# core1.net
KiCad netlist of a schematic drawn in EAGLE
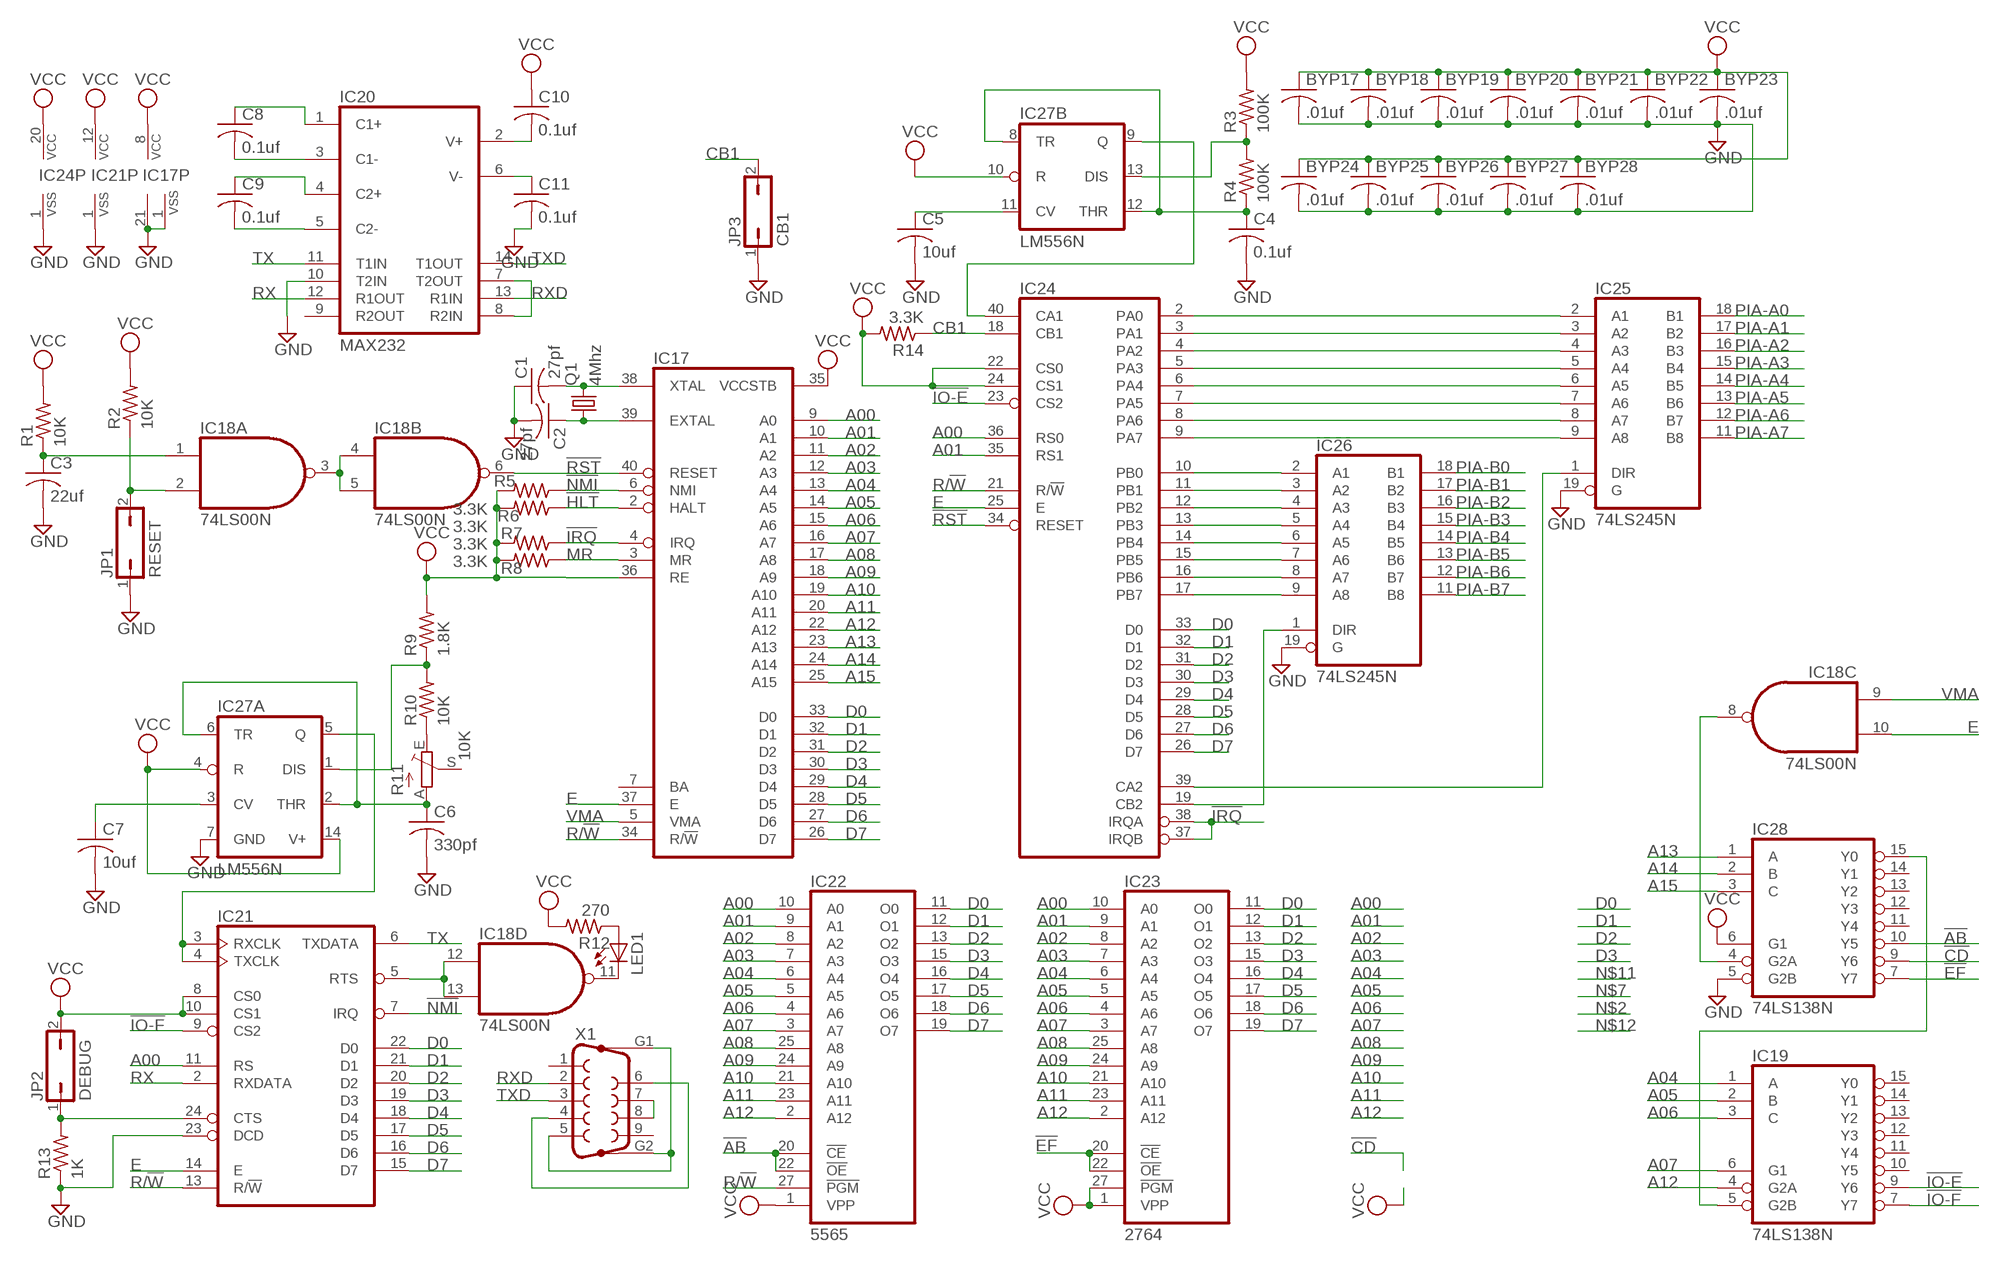
[diagram p0: schematic, sheet 1]
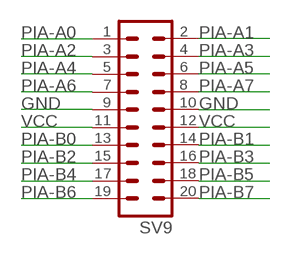
[diagram p1: schematic, sheet 2]

(export (version "E")
  (design (tool "Eeschema 10.0.6"))
  (components
    (comp (ref "BYP17")
      (value ".01uf")
      (footprint "eagle-import:C050-025X075")
      (libsource (lib "eagle-import") (part "C-US050-025X075"))
    )
    (comp (ref "BYP18")
      (value ".01uf")
      (footprint "eagle-import:C050-025X075")
      (libsource (lib "eagle-import") (part "C-US050-025X075"))
    )
    (comp (ref "BYP19")
      (value ".01uf")
      (footprint "eagle-import:C050-025X075")
      (libsource (lib "eagle-import") (part "C-US050-025X075"))
    )
    (comp (ref "BYP20")
      (value ".01uf")
      (footprint "eagle-import:C050-025X075")
      (libsource (lib "eagle-import") (part "C-US050-025X075"))
    )
    (comp (ref "BYP21")
      (value ".01uf")
      (footprint "eagle-import:C050-025X075")
      (libsource (lib "eagle-import") (part "C-US050-025X075"))
    )
    (comp (ref "BYP22")
      (value ".01uf")
      (footprint "eagle-import:C050-025X075")
      (libsource (lib "eagle-import") (part "C-US050-025X075"))
    )
    (comp (ref "BYP23")
      (value ".01uf")
      (footprint "eagle-import:C050-025X075")
      (libsource (lib "eagle-import") (part "C-US050-025X075"))
    )
    (comp (ref "BYP24")
      (value ".01uf")
      (footprint "eagle-import:C050-025X075")
      (libsource (lib "eagle-import") (part "C-US050-025X075"))
    )
    (comp (ref "BYP25")
      (value ".01uf")
      (footprint "eagle-import:C050-025X075")
      (libsource (lib "eagle-import") (part "C-US050-025X075"))
    )
    (comp (ref "BYP26")
      (value ".01uf")
      (footprint "eagle-import:C050-025X075")
      (libsource (lib "eagle-import") (part "C-US050-025X075"))
    )
    (comp (ref "BYP27")
      (value ".01uf")
      (footprint "eagle-import:C050-025X075")
      (libsource (lib "eagle-import") (part "C-US050-025X075"))
    )
    (comp (ref "BYP28")
      (value ".01uf")
      (footprint "eagle-import:C050-025X075")
      (libsource (lib "eagle-import") (part "C-US050-025X075"))
    )
    (comp (ref "C1")
      (value "27pf")
      (footprint "eagle-import:C050-025X075")
      (libsource (lib "eagle-import") (part "C-US050-025X075"))
    )
    (comp (ref "C2")
      (value "27pf")
      (footprint "eagle-import:C050-025X075")
      (libsource (lib "eagle-import") (part "C-US050-025X075"))
    )
    (comp (ref "C3")
      (value "22uf")
      (footprint "eagle-import:C102-043X133")
      (libsource (lib "eagle-import") (part "C-US102-043X133"))
    )
    (comp (ref "C4")
      (value "0.1uf")
      (footprint "eagle-import:C050-025X075")
      (libsource (lib "eagle-import") (part "C-US050-025X075"))
    )
    (comp (ref "C5")
      (value "10uf")
      (footprint "eagle-import:C050-025X075")
      (libsource (lib "eagle-import") (part "C-US050-025X075"))
    )
    (comp (ref "C6")
      (value "330pf")
      (footprint "eagle-import:C050-025X075")
      (libsource (lib "eagle-import") (part "C-US050-025X075"))
    )
    (comp (ref "C7")
      (value "10uf")
      (footprint "eagle-import:C050-025X075")
      (libsource (lib "eagle-import") (part "C-US050-025X075"))
    )
    (comp (ref "C8")
      (value "0.1uf")
      (footprint "eagle-import:C050-025X075")
      (libsource (lib "eagle-import") (part "C-US050-025X075"))
    )
    (comp (ref "C9")
      (value "0.1uf")
      (footprint "eagle-import:C050-025X075")
      (libsource (lib "eagle-import") (part "C-US050-025X075"))
    )
    (comp (ref "C10")
      (value "0.1uf")
      (footprint "eagle-import:C050-025X075")
      (libsource (lib "eagle-import") (part "C-US050-025X075"))
    )
    (comp (ref "C11")
      (value "0.1uf")
      (footprint "eagle-import:C050-025X075")
      (libsource (lib "eagle-import") (part "C-US050-025X075"))
    )
    (comp (ref "IC17")
      (value "6802")
      (footprint "eagle-import:DIL40")
      (libsource (lib "eagle-import") (part "6802"))
    )
    (comp (ref "IC18")
      (value "74LS00N")
      (footprint "eagle-import:DIL14")
      (libsource (lib "eagle-import") (part "7400NLS"))
    )
    (comp (ref "IC19")
      (value "74LS138N")
      (footprint "eagle-import:DIL16")
      (libsource (lib "eagle-import") (part "74138NLS"))
    )
    (comp (ref "IC20")
      (value "MAX232")
      (footprint "eagle-import:DIL16")
      (fields (field (name "MF") "MAXIM") (field (name "MPN") "MAX232ACPE+"))
      (libsource (lib "eagle-import") (part "MAX232"))
    )
    (comp (ref "IC21")
      (value "6850")
      (footprint "eagle-import:DIL24")
      (fields (field (name "MF") "NTE ELECTRONICS") (field (name "MPN") "NTE6850"))
      (libsource (lib "eagle-import") (part "6850"))
    )
    (comp (ref "IC22")
      (value "5565")
      (footprint "eagle-import:DIL28")
      (libsource (lib "eagle-import") (part "2764"))
    )
    (comp (ref "IC23")
      (value "2764")
      (footprint "eagle-import:DIL28")
      (libsource (lib "eagle-import") (part "2764"))
    )
    (comp (ref "IC24")
      (value "6821")
      (footprint "eagle-import:DIL40")
      (fields (field (name "MF") "NTE ELECTRONICS") (field (name "MPN") "NTE6821"))
      (libsource (lib "eagle-import") (part "6821"))
    )
    (comp (ref "IC25")
      (value "74LS245N")
      (footprint "eagle-import:DIL20")
      (libsource (lib "eagle-import") (part "74245NLS"))
    )
    (comp (ref "IC26")
      (value "74LS245N")
      (footprint "eagle-import:DIL20")
      (libsource (lib "eagle-import") (part "74245NLS"))
    )
    (comp (ref "IC27")
      (value "LM556N")
      (footprint "eagle-import:DIL14")
      (libsource (lib "eagle-import") (part "556NLM"))
    )
    (comp (ref "IC28")
      (value "74LS138N")
      (footprint "eagle-import:DIL16")
      (libsource (lib "eagle-import") (part "74138NLS"))
    )
    (comp (ref "JP1")
      (value "RESET")
      (footprint "eagle-import:JP1")
      (libsource (lib "eagle-import") (part "JP1Q"))
    )
    (comp (ref "JP2")
      (value "DEBUG")
      (footprint "eagle-import:JP1")
      (libsource (lib "eagle-import") (part "JP1Q"))
    )
    (comp (ref "JP3")
      (value "CB1")
      (footprint "eagle-import:JP1")
      (libsource (lib "eagle-import") (part "JP1Q"))
    )
    (comp (ref "LED1")
      (value "LED3MM")
      (footprint "eagle-import:LED3MM")
      (libsource (lib "eagle-import") (part "LED3MM"))
    )
    (comp (ref "Q1")
      (value "4Mhz")
      (footprint "eagle-import:HC18U-V")
      (libsource (lib "eagle-import") (part "CRYSTALHC18U-V"))
    )
    (comp (ref "R1")
      (value "10K")
      (footprint "eagle-import:0207_7")
      (libsource (lib "eagle-import") (part "R-US_0207/7"))
    )
    (comp (ref "R2")
      (value "10K")
      (footprint "eagle-import:0207_7")
      (libsource (lib "eagle-import") (part "R-US_0207/7"))
    )
    (comp (ref "R3")
      (value "100K")
      (footprint "eagle-import:0207_7")
      (libsource (lib "eagle-import") (part "R-US_0207/7"))
    )
    (comp (ref "R4")
      (value "100K")
      (footprint "eagle-import:0207_7")
      (libsource (lib "eagle-import") (part "R-US_0207/7"))
    )
    (comp (ref "R5")
      (value "3.3K")
      (footprint "eagle-import:0207_7")
      (libsource (lib "eagle-import") (part "R-US_0207/7"))
    )
    (comp (ref "R6")
      (value "3.3K")
      (footprint "eagle-import:0207_7")
      (libsource (lib "eagle-import") (part "R-US_0207/7"))
    )
    (comp (ref "R7")
      (value "3.3K")
      (footprint "eagle-import:0207_7")
      (libsource (lib "eagle-import") (part "R-US_0207/7"))
    )
    (comp (ref "R8")
      (value "3.3K")
      (footprint "eagle-import:0207_7")
      (libsource (lib "eagle-import") (part "R-US_0207/7"))
    )
    (comp (ref "R9")
      (value "1.8K")
      (footprint "eagle-import:0207_7")
      (libsource (lib "eagle-import") (part "R-US_0207/7"))
    )
    (comp (ref "R10")
      (value "10K")
      (footprint "eagle-import:0207_7")
      (libsource (lib "eagle-import") (part "R-US_0207/7"))
    )
    (comp (ref "R11")
      (value "10K")
      (footprint "eagle-import:SP19L")
      (libsource (lib "eagle-import") (part "TRIM_EU-B90P"))
    )
    (comp (ref "R12")
      (value "270")
      (footprint "eagle-import:0207_7")
      (libsource (lib "eagle-import") (part "R-US_0207/7"))
    )
    (comp (ref "R13")
      (value "1K")
      (footprint "eagle-import:0207_7")
      (libsource (lib "eagle-import") (part "R-US_0207/7"))
    )
    (comp (ref "R14")
      (value "3.3K")
      (footprint "eagle-import:0207_7")
      (libsource (lib "eagle-import") (part "R-US_0207/7"))
    )
    (comp (ref "X1")
      (value "F09HP")
      (footprint "eagle-import:F09HP")
      (libsource (lib "eagle-import") (part "F09HP"))
    )
    (comp (ref "SV9")
      (value "MA10-2")
      (footprint "eagle-import:MA10-2")
      (libsource (lib "eagle-import") (part "MA10-2"))
    )
  )
  (nets
    (net (code "1") (name "A00") (class "Default")
      (node (ref "IC17") (pin "9") (pinfunction "A0_9") (pintype "output"))
      (node (ref "IC21") (pin "11") (pinfunction "RS_11") (pintype "input"))
      (node (ref "IC22") (pin "10") (pinfunction "A0_10") (pintype "input"))
      (node (ref "IC23") (pin "10") (pinfunction "A0_10") (pintype "input"))
      (node (ref "IC24") (pin "36") (pinfunction "RS0_36") (pintype "input"))
    )
    (net (code "2") (name "A01") (class "Default")
      (node (ref "IC17") (pin "10") (pinfunction "A1_10") (pintype "output"))
      (node (ref "IC22") (pin "9") (pinfunction "A1_9") (pintype "input"))
      (node (ref "IC23") (pin "9") (pinfunction "A1_9") (pintype "input"))
      (node (ref "IC24") (pin "35") (pinfunction "RS1_35") (pintype "input"))
    )
    (net (code "3") (name "A02") (class "Default")
      (node (ref "IC17") (pin "11") (pinfunction "A2_11") (pintype "output"))
      (node (ref "IC22") (pin "8") (pinfunction "A2_8") (pintype "input"))
      (node (ref "IC23") (pin "8") (pinfunction "A2_8") (pintype "input"))
    )
    (net (code "4") (name "A03") (class "Default")
      (node (ref "IC17") (pin "12") (pinfunction "A3_12") (pintype "output"))
      (node (ref "IC22") (pin "7") (pinfunction "A3_7") (pintype "input"))
      (node (ref "IC23") (pin "7") (pinfunction "A3_7") (pintype "input"))
    )
    (net (code "5") (name "A04") (class "Default")
      (node (ref "IC17") (pin "13") (pinfunction "A4_13") (pintype "output"))
      (node (ref "IC19") (pin "1") (pinfunction "A_1") (pintype "input"))
      (node (ref "IC22") (pin "6") (pinfunction "A4_6") (pintype "input"))
      (node (ref "IC23") (pin "6") (pinfunction "A4_6") (pintype "input"))
    )
    (net (code "6") (name "A05") (class "Default")
      (node (ref "IC17") (pin "14") (pinfunction "A5_14") (pintype "output"))
      (node (ref "IC19") (pin "2") (pinfunction "B_2") (pintype "input"))
      (node (ref "IC22") (pin "5") (pinfunction "A5_5") (pintype "input"))
      (node (ref "IC23") (pin "5") (pinfunction "A5_5") (pintype "input"))
    )
    (net (code "7") (name "A06") (class "Default")
      (node (ref "IC17") (pin "15") (pinfunction "A6_15") (pintype "output"))
      (node (ref "IC19") (pin "3") (pinfunction "C_3") (pintype "input"))
      (node (ref "IC22") (pin "4") (pinfunction "A6_4") (pintype "input"))
      (node (ref "IC23") (pin "4") (pinfunction "A6_4") (pintype "input"))
    )
    (net (code "8") (name "A07") (class "Default")
      (node (ref "IC17") (pin "16") (pinfunction "A7_16") (pintype "output"))
      (node (ref "IC19") (pin "6") (pinfunction "G1_6") (pintype "input"))
      (node (ref "IC22") (pin "3") (pinfunction "A7_3") (pintype "input"))
      (node (ref "IC23") (pin "3") (pinfunction "A7_3") (pintype "input"))
    )
    (net (code "9") (name "A08") (class "Default")
      (node (ref "IC17") (pin "17") (pinfunction "A8_17") (pintype "output"))
      (node (ref "IC22") (pin "25") (pinfunction "A8_25") (pintype "input"))
      (node (ref "IC23") (pin "25") (pinfunction "A8_25") (pintype "input"))
    )
    (net (code "10") (name "A09") (class "Default")
      (node (ref "IC17") (pin "18") (pinfunction "A9_18") (pintype "output"))
      (node (ref "IC22") (pin "24") (pinfunction "A9_24") (pintype "input"))
      (node (ref "IC23") (pin "24") (pinfunction "A9_24") (pintype "input"))
    )
    (net (code "11") (name "A10") (class "Default")
      (node (ref "IC17") (pin "19") (pinfunction "A10_19") (pintype "output"))
      (node (ref "IC22") (pin "21") (pinfunction "A10_21") (pintype "input"))
      (node (ref "IC23") (pin "21") (pinfunction "A10_21") (pintype "input"))
    )
    (net (code "12") (name "A11") (class "Default")
      (node (ref "IC17") (pin "20") (pinfunction "A11_20") (pintype "output"))
      (node (ref "IC22") (pin "23") (pinfunction "A11_23") (pintype "input"))
      (node (ref "IC23") (pin "23") (pinfunction "A11_23") (pintype "input"))
    )
    (net (code "13") (name "A12") (class "Default")
      (node (ref "IC17") (pin "22") (pinfunction "A12_22") (pintype "output"))
      (node (ref "IC19") (pin "4") (pinfunction "G2A_4") (pintype "input"))
      (node (ref "IC22") (pin "2") (pinfunction "A12_2") (pintype "input"))
      (node (ref "IC23") (pin "2") (pinfunction "A12_2") (pintype "input"))
    )
    (net (code "14") (name "A13") (class "Default")
      (node (ref "IC17") (pin "23") (pinfunction "A13_23") (pintype "output"))
      (node (ref "IC28") (pin "1") (pinfunction "A_1") (pintype "input"))
    )
    (net (code "15") (name "A14") (class "Default")
      (node (ref "IC17") (pin "24") (pinfunction "A14_24") (pintype "output"))
      (node (ref "IC28") (pin "2") (pinfunction "B_2") (pintype "input"))
    )
    (net (code "16") (name "A15") (class "Default")
      (node (ref "IC17") (pin "25") (pinfunction "A15_25") (pintype "output"))
      (node (ref "IC28") (pin "3") (pinfunction "C_3") (pintype "input"))
    )
    (net (code "17") (name "CB1") (class "Default")
      (node (ref "IC24") (pin "18") (pinfunction "CB1_18") (pintype "input"))
      (node (ref "JP3") (pin "2") (pinfunction "2_2") (pintype "passive"))
      (node (ref "R14") (pin "1") (pinfunction "1_1") (pintype "passive"))
    )
    (net (code "18") (name "D0") (class "Default")
      (node (ref "IC17") (pin "33") (pinfunction "D0_33") (pintype "bidirectional"))
      (node (ref "IC21") (pin "22") (pinfunction "D0_22") (pintype "bidirectional"))
      (node (ref "IC22") (pin "11") (pinfunction "O0_11") (pintype "tri_state"))
      (node (ref "IC23") (pin "11") (pinfunction "O0_11") (pintype "tri_state"))
      (node (ref "IC24") (pin "33") (pinfunction "D0_33") (pintype "bidirectional"))
    )
    (net (code "19") (name "D1") (class "Default")
      (node (ref "IC17") (pin "32") (pinfunction "D1_32") (pintype "bidirectional"))
      (node (ref "IC21") (pin "21") (pinfunction "D1_21") (pintype "bidirectional"))
      (node (ref "IC22") (pin "12") (pinfunction "O1_12") (pintype "tri_state"))
      (node (ref "IC23") (pin "12") (pinfunction "O1_12") (pintype "tri_state"))
      (node (ref "IC24") (pin "32") (pinfunction "D1_32") (pintype "bidirectional"))
    )
    (net (code "20") (name "D2") (class "Default")
      (node (ref "IC17") (pin "31") (pinfunction "D2_31") (pintype "bidirectional"))
      (node (ref "IC21") (pin "20") (pinfunction "D2_20") (pintype "bidirectional"))
      (node (ref "IC22") (pin "13") (pinfunction "O2_13") (pintype "tri_state"))
      (node (ref "IC23") (pin "13") (pinfunction "O2_13") (pintype "tri_state"))
      (node (ref "IC24") (pin "31") (pinfunction "D2_31") (pintype "bidirectional"))
    )
    (net (code "21") (name "D3") (class "Default")
      (node (ref "IC17") (pin "30") (pinfunction "D3_30") (pintype "bidirectional"))
      (node (ref "IC21") (pin "19") (pinfunction "D3_19") (pintype "bidirectional"))
      (node (ref "IC22") (pin "15") (pinfunction "O3_15") (pintype "tri_state"))
      (node (ref "IC23") (pin "15") (pinfunction "O3_15") (pintype "tri_state"))
      (node (ref "IC24") (pin "30") (pinfunction "D3_30") (pintype "bidirectional"))
    )
    (net (code "22") (name "D4") (class "Default")
      (node (ref "IC17") (pin "29") (pinfunction "D4_29") (pintype "bidirectional"))
      (node (ref "IC21") (pin "18") (pinfunction "D4_18") (pintype "bidirectional"))
      (node (ref "IC22") (pin "16") (pinfunction "O4_16") (pintype "tri_state"))
      (node (ref "IC23") (pin "16") (pinfunction "O4_16") (pintype "tri_state"))
      (node (ref "IC24") (pin "29") (pinfunction "D4_29") (pintype "bidirectional"))
    )
    (net (code "23") (name "D5") (class "Default")
      (node (ref "IC17") (pin "28") (pinfunction "D5_28") (pintype "bidirectional"))
      (node (ref "IC21") (pin "17") (pinfunction "D5_17") (pintype "bidirectional"))
      (node (ref "IC22") (pin "17") (pinfunction "O5_17") (pintype "tri_state"))
      (node (ref "IC23") (pin "17") (pinfunction "O5_17") (pintype "tri_state"))
      (node (ref "IC24") (pin "28") (pinfunction "D5_28") (pintype "bidirectional"))
    )
    (net (code "24") (name "D6") (class "Default")
      (node (ref "IC17") (pin "27") (pinfunction "D6_27") (pintype "bidirectional"))
      (node (ref "IC21") (pin "16") (pinfunction "D6_16") (pintype "bidirectional"))
      (node (ref "IC22") (pin "18") (pinfunction "O6_18") (pintype "tri_state"))
      (node (ref "IC23") (pin "18") (pinfunction "O6_18") (pintype "tri_state"))
      (node (ref "IC24") (pin "27") (pinfunction "D6_27") (pintype "bidirectional"))
    )
    (net (code "25") (name "D7") (class "Default")
      (node (ref "IC17") (pin "26") (pinfunction "D7_26") (pintype "bidirectional"))
      (node (ref "IC21") (pin "15") (pinfunction "D7_15") (pintype "bidirectional"))
      (node (ref "IC22") (pin "19") (pinfunction "O7_19") (pintype "tri_state"))
      (node (ref "IC23") (pin "19") (pinfunction "O7_19") (pintype "tri_state"))
      (node (ref "IC24") (pin "26") (pinfunction "D7_26") (pintype "bidirectional"))
    )
    (net (code "26") (name "E") (class "Default")
      (node (ref "IC17") (pin "37") (pinfunction "E_37") (pintype "output"))
      (node (ref "IC18") (pin "10") (pinfunction "I1_10") (pintype "input"))
      (node (ref "IC21") (pin "14") (pinfunction "E_14") (pintype "input"))
      (node (ref "IC24") (pin "25") (pinfunction "E_25") (pintype "input"))
    )
    (net (code "27") (name "GND") (class "Default")
      (node (ref "BYP17") (pin "2") (pinfunction "2_2") (pintype "passive"))
      (node (ref "BYP18") (pin "2") (pinfunction "2_2") (pintype "passive"))
      (node (ref "BYP19") (pin "2") (pinfunction "2_2") (pintype "passive"))
      (node (ref "BYP20") (pin "2") (pinfunction "2_2") (pintype "passive"))
      (node (ref "BYP21") (pin "2") (pinfunction "2_2") (pintype "passive"))
      (node (ref "BYP22") (pin "2") (pinfunction "2_2") (pintype "passive"))
      (node (ref "BYP23") (pin "2") (pinfunction "2_2") (pintype "passive"))
      (node (ref "BYP24") (pin "2") (pinfunction "2_2") (pintype "passive"))
      (node (ref "BYP25") (pin "2") (pinfunction "2_2") (pintype "passive"))
      (node (ref "BYP26") (pin "2") (pinfunction "2_2") (pintype "passive"))
      (node (ref "BYP27") (pin "2") (pinfunction "2_2") (pintype "passive"))
      (node (ref "BYP28") (pin "2") (pinfunction "2_2") (pintype "passive"))
      (node (ref "C1") (pin "1") (pinfunction "1_1") (pintype "passive"))
      (node (ref "C11") (pin "2") (pinfunction "2_2") (pintype "passive"))
      (node (ref "C2") (pin "2") (pinfunction "2_2") (pintype "passive"))
      (node (ref "C3") (pin "2") (pinfunction "2_2") (pintype "passive"))
      (node (ref "C4") (pin "2") (pinfunction "2_2") (pintype "passive"))
      (node (ref "C5") (pin "2") (pinfunction "2_2") (pintype "passive"))
      (node (ref "C6") (pin "2") (pinfunction "2_2") (pintype "passive"))
      (node (ref "C7") (pin "2") (pinfunction "2_2") (pintype "passive"))
      (node (ref "IC17") (pin "1") (pinfunction "VSS_1") (pintype "power_in"))
      (node (ref "IC17") (pin "21") (pinfunction "VSS_21") (pintype "power_in"))
      (node (ref "IC20") (pin "10") (pinfunction "T2IN_10") (pintype "input"))
      (node (ref "IC21") (pin "1") (pinfunction "VSS_1") (pintype "power_in"))
      (node (ref "IC21") (pin "23") (pinfunction "DCD_23") (pintype "input"))
      (node (ref "IC24") (pin "1") (pinfunction "VSS_1") (pintype "power_in"))
      (node (ref "IC25") (pin "19") (pinfunction "G_19") (pintype "input"))
      (node (ref "IC26") (pin "19") (pinfunction "G_19") (pintype "input"))
      (node (ref "IC27") (pin "7") (pinfunction "GND_7") (pintype "power_in"))
      (node (ref "IC28") (pin "5") (pinfunction "G2B_5") (pintype "input"))
      (node (ref "JP1") (pin "1") (pinfunction "1_1") (pintype "passive"))
      (node (ref "JP3") (pin "1") (pinfunction "1_1") (pintype "passive"))
      (node (ref "R13") (pin "1") (pinfunction "1_1") (pintype "passive"))
      (node (ref "SV9") (pin "10") (pinfunction "10_10") (pintype "passive"))
      (node (ref "SV9") (pin "9") (pinfunction "9_9") (pintype "passive"))
    )
    (net (code "28") (name "MR") (class "Default")
      (node (ref "IC17") (pin "3") (pinfunction "MR_3") (pintype "input"))
      (node (ref "R8") (pin "1") (pinfunction "1_1") (pintype "passive"))
    )
    (net (code "33") (name "Net-(IC17A-EXTAL)") (class "Default")
      (node (ref "C2") (pin "1") (pinfunction "1_1") (pintype "passive"))
      (node (ref "IC17") (pin "39") (pinfunction "EXTAL_39") (pintype "input"))
      (node (ref "Q1") (pin "1") (pinfunction "1_1") (pintype "passive"))
    )
    (net (code "34") (name "Net-(IC17A-XTAL)") (class "Default")
      (node (ref "C1") (pin "2") (pinfunction "2_2") (pintype "passive"))
      (node (ref "IC17") (pin "38") (pinfunction "XTAL_38") (pintype "input"))
      (node (ref "Q1") (pin "2") (pinfunction "2_2") (pintype "passive"))
    )
    (net (code "35") (name "Net-(IC18A-I0)") (class "Default")
      (node (ref "C3") (pin "1") (pinfunction "1_1") (pintype "passive"))
      (node (ref "IC18") (pin "1") (pinfunction "I0_1") (pintype "input"))
      (node (ref "R1") (pin "1") (pinfunction "1_1") (pintype "passive"))
    )
    (net (code "36") (name "Net-(IC18A-I1)") (class "Default")
      (node (ref "IC18") (pin "2") (pinfunction "I1_2") (pintype "input"))
      (node (ref "JP1") (pin "2") (pinfunction "2_2") (pintype "passive"))
      (node (ref "R2") (pin "1") (pinfunction "1_1") (pintype "passive"))
    )
    (net (code "37") (name "Net-(IC18A-O)") (class "Default")
      (node (ref "IC18") (pin "3") (pinfunction "O_3") (pintype "output"))
      (node (ref "IC18") (pin "4") (pinfunction "I0_4") (pintype "input"))
      (node (ref "IC18") (pin "5") (pinfunction "I1_5") (pintype "input"))
    )
    (net (code "38") (name "Net-(IC18C-O)") (class "Default")
      (node (ref "IC18") (pin "8") (pinfunction "O_8") (pintype "output"))
      (node (ref "IC28") (pin "4") (pinfunction "G2A_4") (pintype "input"))
    )
    (net (code "39") (name "Net-(IC18D-I0)") (class "Default")
      (node (ref "IC18") (pin "12") (pinfunction "I0_12") (pintype "input"))
      (node (ref "IC18") (pin "13") (pinfunction "I1_13") (pintype "input"))
      (node (ref "IC21") (pin "5") (pinfunction "RTS_5") (pintype "output"))
    )
    (net (code "40") (name "Net-(IC18D-O)") (class "Default")
      (node (ref "IC18") (pin "11") (pinfunction "O_11") (pintype "output"))
      (node (ref "LED1") (pin "K") (pinfunction "C_K") (pintype "passive"))
    )
    (net (code "41") (name "Net-(IC19A-G2B)") (class "Default")
      (node (ref "IC19") (pin "5") (pinfunction "G2B_5") (pintype "input"))
      (node (ref "IC28") (pin "15") (pinfunction "Y0_15") (pintype "output"))
    )
    (net (code "42") (name "Net-(IC20A-C1+)") (class "Default")
      (node (ref "C8") (pin "1") (pinfunction "1_1") (pintype "passive"))
      (node (ref "IC20") (pin "1") (pinfunction "C1+_1") (pintype "bidirectional"))
    )
    (net (code "43") (name "Net-(IC20A-C1-)") (class "Default")
      (node (ref "C8") (pin "2") (pinfunction "2_2") (pintype "passive"))
      (node (ref "IC20") (pin "3") (pinfunction "C1-_3") (pintype "bidirectional"))
    )
    (net (code "44") (name "Net-(IC20A-C2+)") (class "Default")
      (node (ref "C9") (pin "1") (pinfunction "1_1") (pintype "passive"))
      (node (ref "IC20") (pin "4") (pinfunction "C2+_4") (pintype "bidirectional"))
    )
    (net (code "45") (name "Net-(IC20A-C2-)") (class "Default")
      (node (ref "C9") (pin "2") (pinfunction "2_2") (pintype "passive"))
      (node (ref "IC20") (pin "5") (pinfunction "C2-_5") (pintype "bidirectional"))
    )
    (net (code "46") (name "Net-(IC20A-R2IN)") (class "Default")
      (node (ref "IC20") (pin "7") (pinfunction "T2OUT_7") (pintype "output"))
      (node (ref "IC20") (pin "8") (pinfunction "R2IN_8") (pintype "input"))
    )
    (net (code "47") (name "Net-(IC20A-V+)") (class "Default")
      (node (ref "C10") (pin "2") (pinfunction "2_2") (pintype "passive"))
      (node (ref "IC20") (pin "2") (pinfunction "V+_2") (pintype "bidirectional"))
    )
    (net (code "48") (name "Net-(IC20A-V-)") (class "Default")
      (node (ref "C11") (pin "1") (pinfunction "1_1") (pintype "passive"))
      (node (ref "IC20") (pin "6") (pinfunction "V-_6") (pintype "bidirectional"))
    )
    (net (code "49") (name "Net-(IC21A-CTS)") (class "Default")
      (node (ref "IC21") (pin "24") (pinfunction "CTS_24") (pintype "input"))
      (node (ref "JP2") (pin "1") (pinfunction "1_1") (pintype "passive"))
      (node (ref "R13") (pin "2") (pinfunction "2_2") (pintype "passive"))
    )
    (net (code "50") (name "Net-(IC21A-RXCLK)") (class "Default")
      (node (ref "IC21") (pin "3") (pinfunction "RXCLK_3") (pintype "input"))
      (node (ref "IC21") (pin "4") (pinfunction "TXCLK_4") (pintype "input"))
      (node (ref "IC27") (pin "5") (pinfunction "Q_5") (pintype "output"))
    )
    (net (code "51") (name "Net-(IC24A-CA1)") (class "Default")
      (node (ref "IC24") (pin "40") (pinfunction "CA1_40") (pintype "input"))
      (node (ref "IC27") (pin "9") (pinfunction "Q_9") (pintype "output"))
    )
    (net (code "52") (name "Net-(IC24A-CA2)") (class "Default")
      (node (ref "IC24") (pin "39") (pinfunction "CA2_39") (pintype "bidirectional"))
      (node (ref "IC25") (pin "1") (pinfunction "DIR_1") (pintype "input"))
    )
    (net (code "53") (name "Net-(IC24A-CB2)") (class "Default")
      (node (ref "IC24") (pin "19") (pinfunction "CB2_19") (pintype "bidirectional"))
      (node (ref "IC26") (pin "1") (pinfunction "DIR_1") (pintype "input"))
    )
    (net (code "54") (name "Net-(IC24A-PA0)") (class "Default")
      (node (ref "IC24") (pin "2") (pinfunction "PA0_2") (pintype "bidirectional"))
      (node (ref "IC25") (pin "2") (pinfunction "A1_2") (pintype "bidirectional"))
    )
    (net (code "55") (name "Net-(IC24A-PA1)") (class "Default")
      (node (ref "IC24") (pin "3") (pinfunction "PA1_3") (pintype "bidirectional"))
      (node (ref "IC25") (pin "3") (pinfunction "A2_3") (pintype "bidirectional"))
    )
    (net (code "56") (name "Net-(IC24A-PA2)") (class "Default")
      (node (ref "IC24") (pin "4") (pinfunction "PA2_4") (pintype "bidirectional"))
      (node (ref "IC25") (pin "4") (pinfunction "A3_4") (pintype "bidirectional"))
    )
    (net (code "57") (name "Net-(IC24A-PA3)") (class "Default")
      (node (ref "IC24") (pin "5") (pinfunction "PA3_5") (pintype "bidirectional"))
      (node (ref "IC25") (pin "5") (pinfunction "A4_5") (pintype "bidirectional"))
    )
    (net (code "58") (name "Net-(IC24A-PA4)") (class "Default")
      (node (ref "IC24") (pin "6") (pinfunction "PA4_6") (pintype "bidirectional"))
      (node (ref "IC25") (pin "6") (pinfunction "A5_6") (pintype "bidirectional"))
    )
    (net (code "59") (name "Net-(IC24A-PA5)") (class "Default")
      (node (ref "IC24") (pin "7") (pinfunction "PA5_7") (pintype "bidirectional"))
      (node (ref "IC25") (pin "7") (pinfunction "A6_7") (pintype "bidirectional"))
    )
    (net (code "60") (name "Net-(IC24A-PA6)") (class "Default")
      (node (ref "IC24") (pin "8") (pinfunction "PA6_8") (pintype "bidirectional"))
      (node (ref "IC25") (pin "8") (pinfunction "A7_8") (pintype "bidirectional"))
    )
    (net (code "61") (name "Net-(IC24A-PA7)") (class "Default")
      (node (ref "IC24") (pin "9") (pinfunction "PA7_9") (pintype "bidirectional"))
      (node (ref "IC25") (pin "9") (pinfunction "A8_9") (pintype "bidirectional"))
    )
    (net (code "62") (name "Net-(IC24A-PB0)") (class "Default")
      (node (ref "IC24") (pin "10") (pinfunction "PB0_10") (pintype "bidirectional"))
      (node (ref "IC26") (pin "2") (pinfunction "A1_2") (pintype "bidirectional"))
    )
    (net (code "63") (name "Net-(IC24A-PB1)") (class "Default")
      (node (ref "IC24") (pin "11") (pinfunction "PB1_11") (pintype "bidirectional"))
      (node (ref "IC26") (pin "3") (pinfunction "A2_3") (pintype "bidirectional"))
    )
    (net (code "64") (name "Net-(IC24A-PB2)") (class "Default")
      (node (ref "IC24") (pin "12") (pinfunction "PB2_12") (pintype "bidirectional"))
      (node (ref "IC26") (pin "4") (pinfunction "A3_4") (pintype "bidirectional"))
    )
    (net (code "65") (name "Net-(IC24A-PB3)") (class "Default")
      (node (ref "IC24") (pin "13") (pinfunction "PB3_13") (pintype "bidirectional"))
      (node (ref "IC26") (pin "5") (pinfunction "A4_5") (pintype "bidirectional"))
    )
    (net (code "66") (name "Net-(IC24A-PB4)") (class "Default")
      (node (ref "IC24") (pin "14") (pinfunction "PB4_14") (pintype "bidirectional"))
      (node (ref "IC26") (pin "6") (pinfunction "A5_6") (pintype "bidirectional"))
    )
    (net (code "67") (name "Net-(IC24A-PB5)") (class "Default")
      (node (ref "IC24") (pin "15") (pinfunction "PB5_15") (pintype "bidirectional"))
      (node (ref "IC26") (pin "7") (pinfunction "A6_7") (pintype "bidirectional"))
    )
    (net (code "68") (name "Net-(IC24A-PB6)") (class "Default")
      (node (ref "IC24") (pin "16") (pinfunction "PB6_16") (pintype "bidirectional"))
      (node (ref "IC26") (pin "8") (pinfunction "A7_8") (pintype "bidirectional"))
    )
    (net (code "69") (name "Net-(IC24A-PB7)") (class "Default")
      (node (ref "IC24") (pin "17") (pinfunction "PB7_17") (pintype "bidirectional"))
      (node (ref "IC26") (pin "9") (pinfunction "A8_9") (pintype "bidirectional"))
    )
    (net (code "70") (name "Net-(IC27A-CV)") (class "Default")
      (node (ref "C7") (pin "1") (pinfunction "1_1") (pintype "passive"))
      (node (ref "IC27") (pin "3") (pinfunction "CV_3") (pintype "input"))
    )
    (net (code "71") (name "Net-(IC27A-DIS)") (class "Default")
      (node (ref "IC27") (pin "1") (pinfunction "DIS_1") (pintype "input"))
      (node (ref "R10") (pin "2") (pinfunction "2_2") (pintype "passive"))
      (node (ref "R9") (pin "1") (pinfunction "1_1") (pintype "passive"))
    )
    (net (code "72") (name "Net-(IC27A-THR)") (class "Default")
      (node (ref "C6") (pin "1") (pinfunction "1_1") (pintype "passive"))
      (node (ref "IC27") (pin "2") (pinfunction "THR_2") (pintype "input"))
      (node (ref "IC27") (pin "6") (pinfunction "TR_6") (pintype "input"))
      (node (ref "R11") (pin "A") (pinfunction "A_A") (pintype "passive"))
    )
    (net (code "73") (name "Net-(IC27B-CV)") (class "Default")
      (node (ref "C5") (pin "1") (pinfunction "1_1") (pintype "passive"))
      (node (ref "IC27") (pin "11") (pinfunction "CV_11") (pintype "input"))
    )
    (net (code "74") (name "Net-(IC27B-DIS)") (class "Default")
      (node (ref "IC27") (pin "13") (pinfunction "DIS_13") (pintype "input"))
      (node (ref "R3") (pin "1") (pinfunction "1_1") (pintype "passive"))
      (node (ref "R4") (pin "2") (pinfunction "2_2") (pintype "passive"))
    )
    (net (code "75") (name "Net-(IC27B-THR)") (class "Default")
      (node (ref "C4") (pin "1") (pinfunction "1_1") (pintype "passive"))
      (node (ref "IC27") (pin "12") (pinfunction "THR_12") (pintype "input"))
      (node (ref "IC27") (pin "8") (pinfunction "TR_8") (pintype "input"))
      (node (ref "R4") (pin "1") (pinfunction "1_1") (pintype "passive"))
    )
    (net (code "76") (name "Net-(LED1-PadA)") (class "Default")
      (node (ref "LED1") (pin "A") (pinfunction "A_A") (pintype "passive"))
      (node (ref "R12") (pin "1") (pinfunction "1_1") (pintype "passive"))
    )
    (net (code "77") (name "Net-(R10-Pad1)") (class "Default")
      (node (ref "R10") (pin "1") (pinfunction "1_1") (pintype "passive"))
      (node (ref "R11") (pin "E") (pinfunction "E_E") (pintype "passive"))
    )
    (net (code "78") (name "Net-(X1-Pad4)") (class "Default")
      (node (ref "X1") (pin "4") (pinfunction "4_4") (pintype "passive"))
      (node (ref "X1") (pin "6") (pinfunction "6_6") (pintype "passive"))
    )
    (net (code "79") (name "Net-(X1-Pad5)") (class "Default")
      (node (ref "X1") (pin "5") (pinfunction "5_5") (pintype "passive"))
      (node (ref "X1") (pin "G1") (pinfunction "G1_G1") (pintype "passive"))
      (node (ref "X1") (pin "G2") (pinfunction "G2_G2") (pintype "passive"))
    )
    (net (code "80") (name "Net-(X1-Pad7)") (class "Default")
      (node (ref "X1") (pin "7") (pinfunction "7_7") (pintype "passive"))
      (node (ref "X1") (pin "8") (pinfunction "8_8") (pintype "passive"))
    )
    (net (code "81") (name "PIA-A0") (class "Default")
      (node (ref "IC25") (pin "18") (pinfunction "B1_18") (pintype "bidirectional"))
      (node (ref "SV9") (pin "1") (pinfunction "1_1") (pintype "passive"))
    )
    (net (code "82") (name "PIA-A1") (class "Default")
      (node (ref "IC25") (pin "17") (pinfunction "B2_17") (pintype "bidirectional"))
      (node (ref "SV9") (pin "2") (pinfunction "2_2") (pintype "passive"))
    )
    (net (code "83") (name "PIA-A2") (class "Default")
      (node (ref "IC25") (pin "16") (pinfunction "B3_16") (pintype "bidirectional"))
      (node (ref "SV9") (pin "3") (pinfunction "3_3") (pintype "passive"))
    )
    (net (code "84") (name "PIA-A3") (class "Default")
      (node (ref "IC25") (pin "15") (pinfunction "B4_15") (pintype "bidirectional"))
      (node (ref "SV9") (pin "4") (pinfunction "4_4") (pintype "passive"))
    )
    (net (code "85") (name "PIA-A4") (class "Default")
      (node (ref "IC25") (pin "14") (pinfunction "B5_14") (pintype "bidirectional"))
      (node (ref "SV9") (pin "5") (pinfunction "5_5") (pintype "passive"))
    )
    (net (code "86") (name "PIA-A5") (class "Default")
      (node (ref "IC25") (pin "13") (pinfunction "B6_13") (pintype "bidirectional"))
      (node (ref "SV9") (pin "6") (pinfunction "6_6") (pintype "passive"))
    )
    (net (code "87") (name "PIA-A6") (class "Default")
      (node (ref "IC25") (pin "12") (pinfunction "B7_12") (pintype "bidirectional"))
      (node (ref "SV9") (pin "7") (pinfunction "7_7") (pintype "passive"))
    )
    (net (code "88") (name "PIA-A7") (class "Default")
      (node (ref "IC25") (pin "11") (pinfunction "B8_11") (pintype "bidirectional"))
      (node (ref "SV9") (pin "8") (pinfunction "8_8") (pintype "passive"))
    )
    (net (code "89") (name "PIA-B0") (class "Default")
      (node (ref "IC26") (pin "18") (pinfunction "B1_18") (pintype "bidirectional"))
      (node (ref "SV9") (pin "13") (pinfunction "13_13") (pintype "passive"))
    )
    (net (code "90") (name "PIA-B1") (class "Default")
      (node (ref "IC26") (pin "17") (pinfunction "B2_17") (pintype "bidirectional"))
      (node (ref "SV9") (pin "14") (pinfunction "14_14") (pintype "passive"))
    )
    (net (code "91") (name "PIA-B2") (class "Default")
      (node (ref "IC26") (pin "16") (pinfunction "B3_16") (pintype "bidirectional"))
      (node (ref "SV9") (pin "15") (pinfunction "15_15") (pintype "passive"))
    )
    (net (code "92") (name "PIA-B3") (class "Default")
      (node (ref "IC26") (pin "15") (pinfunction "B4_15") (pintype "bidirectional"))
      (node (ref "SV9") (pin "16") (pinfunction "16_16") (pintype "passive"))
    )
    (net (code "93") (name "PIA-B4") (class "Default")
      (node (ref "IC26") (pin "14") (pinfunction "B5_14") (pintype "bidirectional"))
      (node (ref "SV9") (pin "17") (pinfunction "17_17") (pintype "passive"))
    )
    (net (code "94") (name "PIA-B5") (class "Default")
      (node (ref "IC26") (pin "13") (pinfunction "B6_13") (pintype "bidirectional"))
      (node (ref "SV9") (pin "18") (pinfunction "18_18") (pintype "passive"))
    )
    (net (code "95") (name "PIA-B6") (class "Default")
      (node (ref "IC26") (pin "12") (pinfunction "B7_12") (pintype "bidirectional"))
      (node (ref "SV9") (pin "19") (pinfunction "19_19") (pintype "passive"))
    )
    (net (code "96") (name "PIA-B7") (class "Default")
      (node (ref "IC26") (pin "11") (pinfunction "B8_11") (pintype "bidirectional"))
      (node (ref "SV9") (pin "20") (pinfunction "20_20") (pintype "passive"))
    )
    (net (code "97") (name "RX") (class "Default")
      (node (ref "IC20") (pin "12") (pinfunction "R1OUT_12") (pintype "output"))
      (node (ref "IC21") (pin "2") (pinfunction "RXDATA_2") (pintype "input"))
    )
    (net (code "98") (name "RXD") (class "Default")
      (node (ref "IC20") (pin "13") (pinfunction "R1IN_13") (pintype "input"))
      (node (ref "X1") (pin "2") (pinfunction "2_2") (pintype "passive"))
    )
    (net (code "99") (name "R{slash}~{W}") (class "Default")
      (node (ref "IC17") (pin "34") (pinfunction "R/~{W}_34") (pintype "output"))
      (node (ref "IC21") (pin "13") (pinfunction "R/~{W}_13") (pintype "input"))
      (node (ref "IC22") (pin "27") (pinfunction "~{PGM}_27") (pintype "input"))
      (node (ref "IC24") (pin "21") (pinfunction "R/~{W}_21") (pintype "input"))
    )
    (net (code "100") (name "TX") (class "Default")
      (node (ref "IC20") (pin "11") (pinfunction "T1IN_11") (pintype "input"))
      (node (ref "IC21") (pin "6") (pinfunction "TXDATA_6") (pintype "output"))
    )
    (net (code "101") (name "TXD") (class "Default")
      (node (ref "IC20") (pin "14") (pinfunction "T1OUT_14") (pintype "output"))
      (node (ref "X1") (pin "3") (pinfunction "3_3") (pintype "passive"))
    )
    (net (code "102") (name "VCC") (class "Default")
      (node (ref "BYP17") (pin "1") (pinfunction "1_1") (pintype "passive"))
      (node (ref "BYP18") (pin "1") (pinfunction "1_1") (pintype "passive"))
      (node (ref "BYP19") (pin "1") (pinfunction "1_1") (pintype "passive"))
      (node (ref "BYP20") (pin "1") (pinfunction "1_1") (pintype "passive"))
      (node (ref "BYP21") (pin "1") (pinfunction "1_1") (pintype "passive"))
      (node (ref "BYP22") (pin "1") (pinfunction "1_1") (pintype "passive"))
      (node (ref "BYP23") (pin "1") (pinfunction "1_1") (pintype "passive"))
      (node (ref "BYP24") (pin "1") (pinfunction "1_1") (pintype "passive"))
      (node (ref "BYP25") (pin "1") (pinfunction "1_1") (pintype "passive"))
      (node (ref "BYP26") (pin "1") (pinfunction "1_1") (pintype "passive"))
      (node (ref "BYP27") (pin "1") (pinfunction "1_1") (pintype "passive"))
      (node (ref "BYP28") (pin "1") (pinfunction "1_1") (pintype "passive"))
      (node (ref "C10") (pin "1") (pinfunction "1_1") (pintype "passive"))
      (node (ref "IC17") (pin "35") (pinfunction "VCCSTB_35") (pintype "input"))
      (node (ref "IC17") (pin "36") (pinfunction "RE_36") (pintype "input"))
      (node (ref "IC17") (pin "8") (pinfunction "VCC_8") (pintype "power_in"))
      (node (ref "IC21") (pin "10") (pinfunction "CS1_10") (pintype "input"))
      (node (ref "IC21") (pin "12") (pinfunction "VCC_12") (pintype "power_in"))
      (node (ref "IC21") (pin "8") (pinfunction "CS0_8") (pintype "input"))
      (node (ref "IC22") (pin "1") (pinfunction "VPP_1") (pintype "input"))
      (node (ref "IC23") (pin "1") (pinfunction "VPP_1") (pintype "input"))
      (node (ref "IC23") (pin "27") (pinfunction "~{PGM}_27") (pintype "input"))
      (node (ref "IC24") (pin "20") (pinfunction "VCC_20") (pintype "power_in"))
      (node (ref "IC24") (pin "22") (pinfunction "CS0_22") (pintype "input"))
      (node (ref "IC24") (pin "24") (pinfunction "CS1_24") (pintype "input"))
      (node (ref "IC27") (pin "10") (pinfunction "R_10") (pintype "input"))
      (node (ref "IC27") (pin "14") (pinfunction "V+_14") (pintype "power_in"))
      (node (ref "IC27") (pin "4") (pinfunction "R_4") (pintype "input"))
      (node (ref "IC28") (pin "6") (pinfunction "G1_6") (pintype "input"))
      (node (ref "JP2") (pin "2") (pinfunction "2_2") (pintype "passive"))
      (node (ref "R1") (pin "2") (pinfunction "2_2") (pintype "passive"))
      (node (ref "R12") (pin "2") (pinfunction "2_2") (pintype "passive"))
      (node (ref "R14") (pin "2") (pinfunction "2_2") (pintype "passive"))
      (node (ref "R2") (pin "2") (pinfunction "2_2") (pintype "passive"))
      (node (ref "R3") (pin "2") (pinfunction "2_2") (pintype "passive"))
      (node (ref "R5") (pin "2") (pinfunction "2_2") (pintype "passive"))
      (node (ref "R6") (pin "2") (pinfunction "2_2") (pintype "passive"))
      (node (ref "R7") (pin "2") (pinfunction "2_2") (pintype "passive"))
      (node (ref "R8") (pin "2") (pinfunction "2_2") (pintype "passive"))
      (node (ref "R9") (pin "2") (pinfunction "2_2") (pintype "passive"))
      (node (ref "SV9") (pin "11") (pinfunction "11_11") (pintype "passive"))
      (node (ref "SV9") (pin "12") (pinfunction "12_12") (pintype "passive"))
    )
    (net (code "103") (name "VMA") (class "Default")
      (node (ref "IC17") (pin "5") (pinfunction "VMA_5") (pintype "output"))
      (node (ref "IC18") (pin "9") (pinfunction "I0_9") (pintype "input"))
    )
    (net (code "104") (name "unconnected-(IC17A-BA-Pad7)") (class "Default")
      (node (ref "IC17") (pin "7") (pinfunction "BA_7") (pintype "output"))
    )
    (net (code "105") (name "unconnected-(IC19A-Y0-Pad15)") (class "Default")
      (node (ref "IC19") (pin "15") (pinfunction "Y0_15") (pintype "output"))
    )
    (net (code "106") (name "unconnected-(IC19A-Y1-Pad14)") (class "Default")
      (node (ref "IC19") (pin "14") (pinfunction "Y1_14") (pintype "output"))
    )
    (net (code "107") (name "unconnected-(IC19A-Y2-Pad13)") (class "Default")
      (node (ref "IC19") (pin "13") (pinfunction "Y2_13") (pintype "output"))
    )
    (net (code "108") (name "unconnected-(IC19A-Y3-Pad12)") (class "Default")
      (node (ref "IC19") (pin "12") (pinfunction "Y3_12") (pintype "output"))
    )
    (net (code "109") (name "unconnected-(IC19A-Y4-Pad11)") (class "Default")
      (node (ref "IC19") (pin "11") (pinfunction "Y4_11") (pintype "output"))
    )
    (net (code "110") (name "unconnected-(IC19A-Y5-Pad10)") (class "Default")
      (node (ref "IC19") (pin "10") (pinfunction "Y5_10") (pintype "output"))
    )
    (net (code "111") (name "unconnected-(IC20A-R2OUT-Pad9)") (class "Default")
      (node (ref "IC20") (pin "9") (pinfunction "R2OUT_9") (pintype "output"))
    )
    (net (code "112") (name "unconnected-(IC28A-Y1-Pad14)") (class "Default")
      (node (ref "IC28") (pin "14") (pinfunction "Y1_14") (pintype "output"))
    )
    (net (code "113") (name "unconnected-(IC28A-Y2-Pad13)") (class "Default")
      (node (ref "IC28") (pin "13") (pinfunction "Y2_13") (pintype "output"))
    )
    (net (code "114") (name "unconnected-(IC28A-Y3-Pad12)") (class "Default")
      (node (ref "IC28") (pin "12") (pinfunction "Y3_12") (pintype "output"))
    )
    (net (code "115") (name "unconnected-(IC28A-Y4-Pad11)") (class "Default")
      (node (ref "IC28") (pin "11") (pinfunction "Y4_11") (pintype "output"))
    )
    (net (code "116") (name "unconnected-(R11-PadS)") (class "Default")
      (node (ref "R11") (pin "S") (pinfunction "S_S") (pintype "passive"))
    )
    (net (code "117") (name "unconnected-(X1-Pad1)") (class "Default")
      (node (ref "X1") (pin "1") (pinfunction "1_1") (pintype "passive"))
    )
    (net (code "118") (name "unconnected-(X1-Pad9)") (class "Default")
      (node (ref "X1") (pin "9") (pinfunction "9_9") (pintype "passive"))
    )
    (net (code "119") (name "~{AB}") (class "Default")
      (node (ref "IC22") (pin "20") (pinfunction "~{CE}_20") (pintype "input"))
      (node (ref "IC22") (pin "22") (pinfunction "~{OE}_22") (pintype "input"))
      (node (ref "IC28") (pin "10") (pinfunction "Y5_10") (pintype "output"))
    )
    (net (code "120") (name "~{CD}") (class "Default")
      (node (ref "IC28") (pin "9") (pinfunction "Y6_9") (pintype "output"))
    )
    (net (code "121") (name "~{EF}") (class "Default")
      (node (ref "IC23") (pin "20") (pinfunction "~{CE}_20") (pintype "input"))
      (node (ref "IC23") (pin "22") (pinfunction "~{OE}_22") (pintype "input"))
      (node (ref "IC28") (pin "7") (pinfunction "Y7_7") (pintype "output"))
    )
    (net (code "122") (name "~{HLT}") (class "Default")
      (node (ref "IC17") (pin "2") (pinfunction "HALT_2") (pintype "input"))
      (node (ref "R5") (pin "1") (pinfunction "1_1") (pintype "passive"))
    )
    (net (code "123") (name "~{IO-E}") (class "Default")
      (node (ref "IC19") (pin "9") (pinfunction "Y6_9") (pintype "output"))
      (node (ref "IC24") (pin "23") (pinfunction "CS2_23") (pintype "input"))
    )
    (net (code "124") (name "~{IO-F}") (class "Default")
      (node (ref "IC19") (pin "7") (pinfunction "Y7_7") (pintype "output"))
      (node (ref "IC21") (pin "9") (pinfunction "CS2_9") (pintype "input"))
    )
    (net (code "125") (name "~{IRQ}") (class "Default")
      (node (ref "IC17") (pin "4") (pinfunction "IRQ_4") (pintype "input"))
      (node (ref "IC24") (pin "37") (pinfunction "IRQB_37") (pintype "open_collector"))
      (node (ref "IC24") (pin "38") (pinfunction "IRQA_38") (pintype "open_collector"))
      (node (ref "R7") (pin "1") (pinfunction "1_1") (pintype "passive"))
    )
    (net (code "126") (name "~{NMI}") (class "Default")
      (node (ref "IC17") (pin "6") (pinfunction "NMI_6") (pintype "input"))
      (node (ref "IC21") (pin "7") (pinfunction "IRQ_7") (pintype "output"))
      (node (ref "R6") (pin "1") (pinfunction "1_1") (pintype "passive"))
    )
    (net (code "127") (name "~{RST}") (class "Default")
      (node (ref "IC17") (pin "40") (pinfunction "RESET_40") (pintype "input"))
      (node (ref "IC18") (pin "6") (pinfunction "O_6") (pintype "output"))
      (node (ref "IC24") (pin "34") (pinfunction "RESET_34") (pintype "input"))
    )
  )
)
